# 5kW_Sensor.net
KiCad netlist of a schematic drawn in Altium Designer
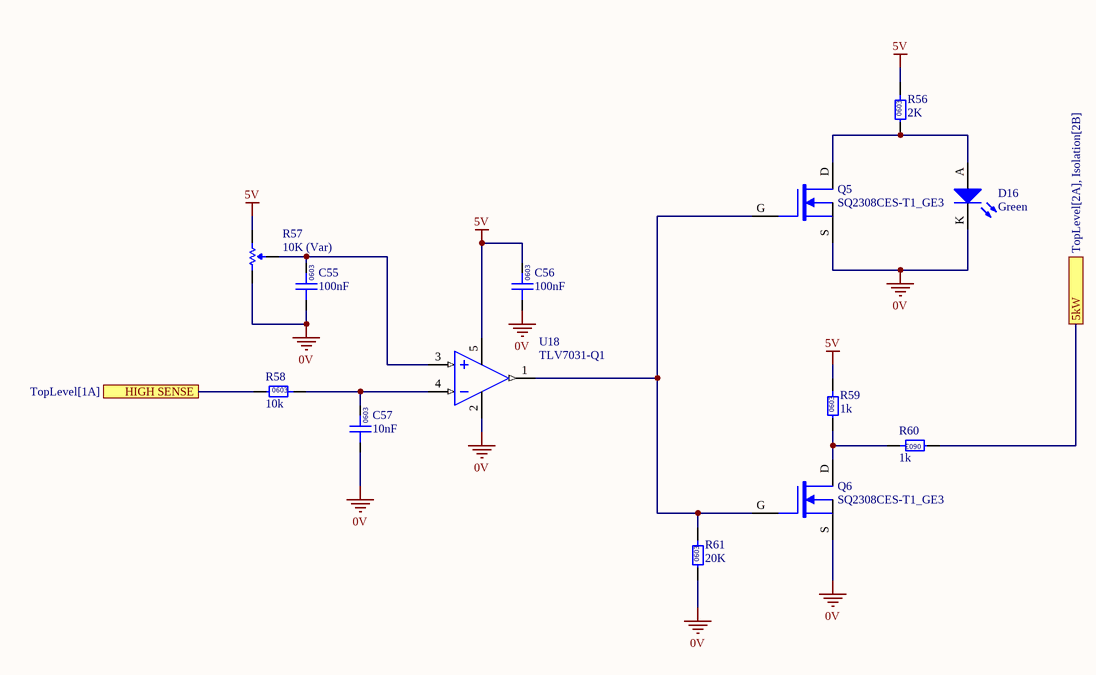
[diagram p0: 5kW Sensor.SchDoc]

(export (version "E")
  (design (tool "Eeschema 10.0.6"))
  (components
    (comp (ref "C55")
      (value "100nF")
      (footprint "0603")
      (fields
        (field (name "PART NUMBER") "GCM188L81H104KA57D")
        (field (name "MANUFACTURER") "muRata")
        (field (name "TOLERANCE") "±10%")
      )
      (libsource (lib "ts_standard_library") (part "Capacitor 0603"))
    )
    (comp (ref "C56")
      (value "100nF")
      (footprint "0603")
      (fields
        (field (name "PART NUMBER") "GCM188L81H104KA57D")
        (field (name "MANUFACTURER") "muRata")
        (field (name "TOLERANCE") "±10%")
      )
      (libsource (lib "ts_standard_library") (part "Capacitor 0603"))
    )
    (comp (ref "C57")
      (value "10nF")
      (footprint "0603")
      (fields
        (field (name "PART NUMBER") "GCM188L81H103KA03D")
        (field (name "MANUFACTURER") "muRata")
        (field (name "TOLERANCE") "±10%")
      )
      (libsource (lib "ts_standard_library") (part "Capacitor 0603"))
    )
    (comp (ref "D16")
      (value "Green")
      (footprint "0805 LED")
      (description "Green LED Indication - Discrete 1.75V 0805 (2012 Metric)")
      (fields (field (name "PART NUMBER") "SML-210FTT86") (field (name "MANUFACTURER") "ROHM Semiconductor"))
      (libsource (lib "ts_standard_library") (part "LED"))
    )
    (comp (ref "Q5")
      (value "SQ2308CES-T1_GE3")
      (footprint "VSHY SOT-23-3")
      (description "MOSFET N-CH 60V 2.3A SOT23")
      (fields
        (field (name "MANUFACTURER") "Vishay Siliconix")
        (field (name "DIGIKEY PART NUMBER") "SQ2308CES-T1_GE3CT-ND")
        (field (name "PUBLISHER") "Altium Limited")
      )
      (libsource (lib "ts_standard_library") (part "MOSFET-N"))
    )
    (comp (ref "Q6")
      (value "SQ2308CES-T1_GE3")
      (footprint "VSHY SOT-23-3")
      (description "MOSFET N-CH 60V 2.3A SOT23")
      (fields
        (field (name "MANUFACTURER") "Vishay Siliconix")
        (field (name "DIGIKEY PART NUMBER") "SQ2308CES-T1_GE3CT-ND")
        (field (name "PUBLISHER") "Altium Limited")
      )
      (libsource (lib "ts_standard_library") (part "MOSFET-N"))
    )
    (comp (ref "R56")
      (value "2K")
      (footprint "0603")
      (fields
        (field (name "PART NUMBER") "RC0603FR-072KL")
        (field (name "MANUFACTURER") "YAGEO")
        (field (name "TOLERANCE") "0.01")
      )
      (libsource (lib "ts_standard_library") (part "Resistor 0603"))
    )
    (comp (ref "R57")
      (value "10K (Var)")
      (footprint "B 3296")
      (fields
        (field (name "PART NUMBER") "3296W-1-103LF")
        (field (name "MANUFACTURER") "Bournes Inc")
        (field (name "TOLERANCE") "0.1")
      )
      (libsource (lib "ts_standard_library") (part "Resistor (Potentiometer)"))
    )
    (comp (ref "R58")
      (value "10k")
      (footprint "0603")
      (fields
        (field (name "PART NUMBER") "RC0603FR-0710KL")
        (field (name "MANUFACTURER") "YAGEO")
        (field (name "TOLERANCE") "0.01")
      )
      (libsource (lib "ts_standard_library") (part "Resistor 0603"))
    )
    (comp (ref "R59")
      (value "1k")
      (footprint "0603")
      (fields
        (field (name "PART NUMBER") "RC0603FR-071KL")
        (field (name "MANUFACTURER") "YAGEO")
        (field (name "TOLERANCE") "0.01")
      )
      (libsource (lib "ts_standard_library") (part "Resistor 0603"))
    )
    (comp (ref "R60")
      (value "1k")
      (footprint "0603")
      (fields
        (field (name "PART NUMBER") "RC0603FR-071KL")
        (field (name "MANUFACTURER") "YAGEO")
        (field (name "TOLERANCE") "0.01")
      )
      (libsource (lib "ts_standard_library") (part "Resistor 0603"))
    )
    (comp (ref "R61")
      (value "20K")
      (footprint "0603")
      (fields
        (field (name "PART NUMBER") "RC0603FR-0720KL")
        (field (name "MANUFACTURER") "YAGEO")
        (field (name "TOLERANCE") "0.01")
      )
      (libsource (lib "ts_standard_library") (part "Resistor 0603"))
    )
    (comp (ref "U18")
      (value "TLV7031-Q1")
      (footprint "TI SOT-23-5")
      (fields
        (field (name "MANUFACTURER") "Texas Instruments")
        (field (name "DIGIKEY PART NUMBER") "296-TLV7031QDBVRQ1CT-ND")
      )
      (libsource (lib "ts_standard_library") (part "TLV7031-Q1"))
    )
  )
  (nets
    (net (code "1") (name "/5kW") (class "Default")
      (node (ref "R60") (pin "1") (pinfunction "1_1") (pintype "passive"))
    )
    (net (code "2") (name "/HIGH SENSE") (class "Default")
      (node (ref "R58") (pin "1") (pinfunction "1_1") (pintype "passive"))
    )
    (net (code "3") (name "0V") (class "Default")
      (node (ref "C55") (pin "1") (pinfunction "1_1") (pintype "passive"))
      (node (ref "C56") (pin "1") (pinfunction "1_1") (pintype "passive"))
      (node (ref "C57") (pin "1") (pinfunction "1_1") (pintype "passive"))
      (node (ref "D16") (pin "K") (pinfunction "K_K") (pintype "passive"))
      (node (ref "Q5") (pin "S") (pinfunction "S_S") (pintype "passive"))
      (node (ref "Q6") (pin "S") (pinfunction "S_S") (pintype "passive"))
      (node (ref "R57") (pin "3") (pinfunction "CW_3") (pintype "passive"))
      (node (ref "R61") (pin "1") (pinfunction "1_1") (pintype "passive"))
      (node (ref "U18") (pin "2") (pinfunction "V-_2") (pintype "power_in"))
    )
    (net (code "4") (name "5V") (class "Default")
      (node (ref "C56") (pin "2") (pinfunction "2_2") (pintype "passive"))
      (node (ref "R56") (pin "2") (pinfunction "2_2") (pintype "passive"))
      (node (ref "R57") (pin "1") (pinfunction "CCW_1") (pintype "passive"))
      (node (ref "R59") (pin "2") (pinfunction "2_2") (pintype "passive"))
      (node (ref "U18") (pin "5") (pinfunction "Vcc_5") (pintype "power_in"))
    )
    (net (code "5") (name "Net-(D16-PadA)") (class "Default")
      (node (ref "D16") (pin "A") (pinfunction "A_A") (pintype "passive"))
      (node (ref "Q5") (pin "D") (pinfunction "D_D") (pintype "passive"))
      (node (ref "R56") (pin "1") (pinfunction "1_1") (pintype "passive"))
    )
    (net (code "6") (name "Net-(Q6-PadD)") (class "Default")
      (node (ref "Q6") (pin "D") (pinfunction "D_D") (pintype "passive"))
      (node (ref "R59") (pin "1") (pinfunction "1_1") (pintype "passive"))
      (node (ref "R60") (pin "2") (pinfunction "2_2") (pintype "passive"))
    )
    (net (code "7") (name "Net-(R57-Wiper)") (class "Default")
      (node (ref "C55") (pin "2") (pinfunction "2_2") (pintype "passive"))
      (node (ref "R57") (pin "2") (pinfunction "Wiper_2") (pintype "passive"))
      (node (ref "U18") (pin "3") (pinfunction "IN+_3") (pintype "input"))
    )
    (net (code "8") (name "Net-(U18-IN-)") (class "Default")
      (node (ref "C57") (pin "2") (pinfunction "2_2") (pintype "passive"))
      (node (ref "R58") (pin "2") (pinfunction "2_2") (pintype "passive"))
      (node (ref "U18") (pin "4") (pinfunction "IN-_4") (pintype "input"))
    )
    (net (code "9") (name "Net-(U18-OUT)") (class "Default")
      (node (ref "Q5") (pin "G") (pinfunction "G_G") (pintype "passive"))
      (node (ref "Q6") (pin "G") (pinfunction "G_G") (pintype "passive"))
      (node (ref "R61") (pin "2") (pinfunction "2_2") (pintype "passive"))
      (node (ref "U18") (pin "1") (pinfunction "OUT_1") (pintype "output"))
    )
  )
)
